# board.net
KiCad netlist of a schematic drawn in EAGLE
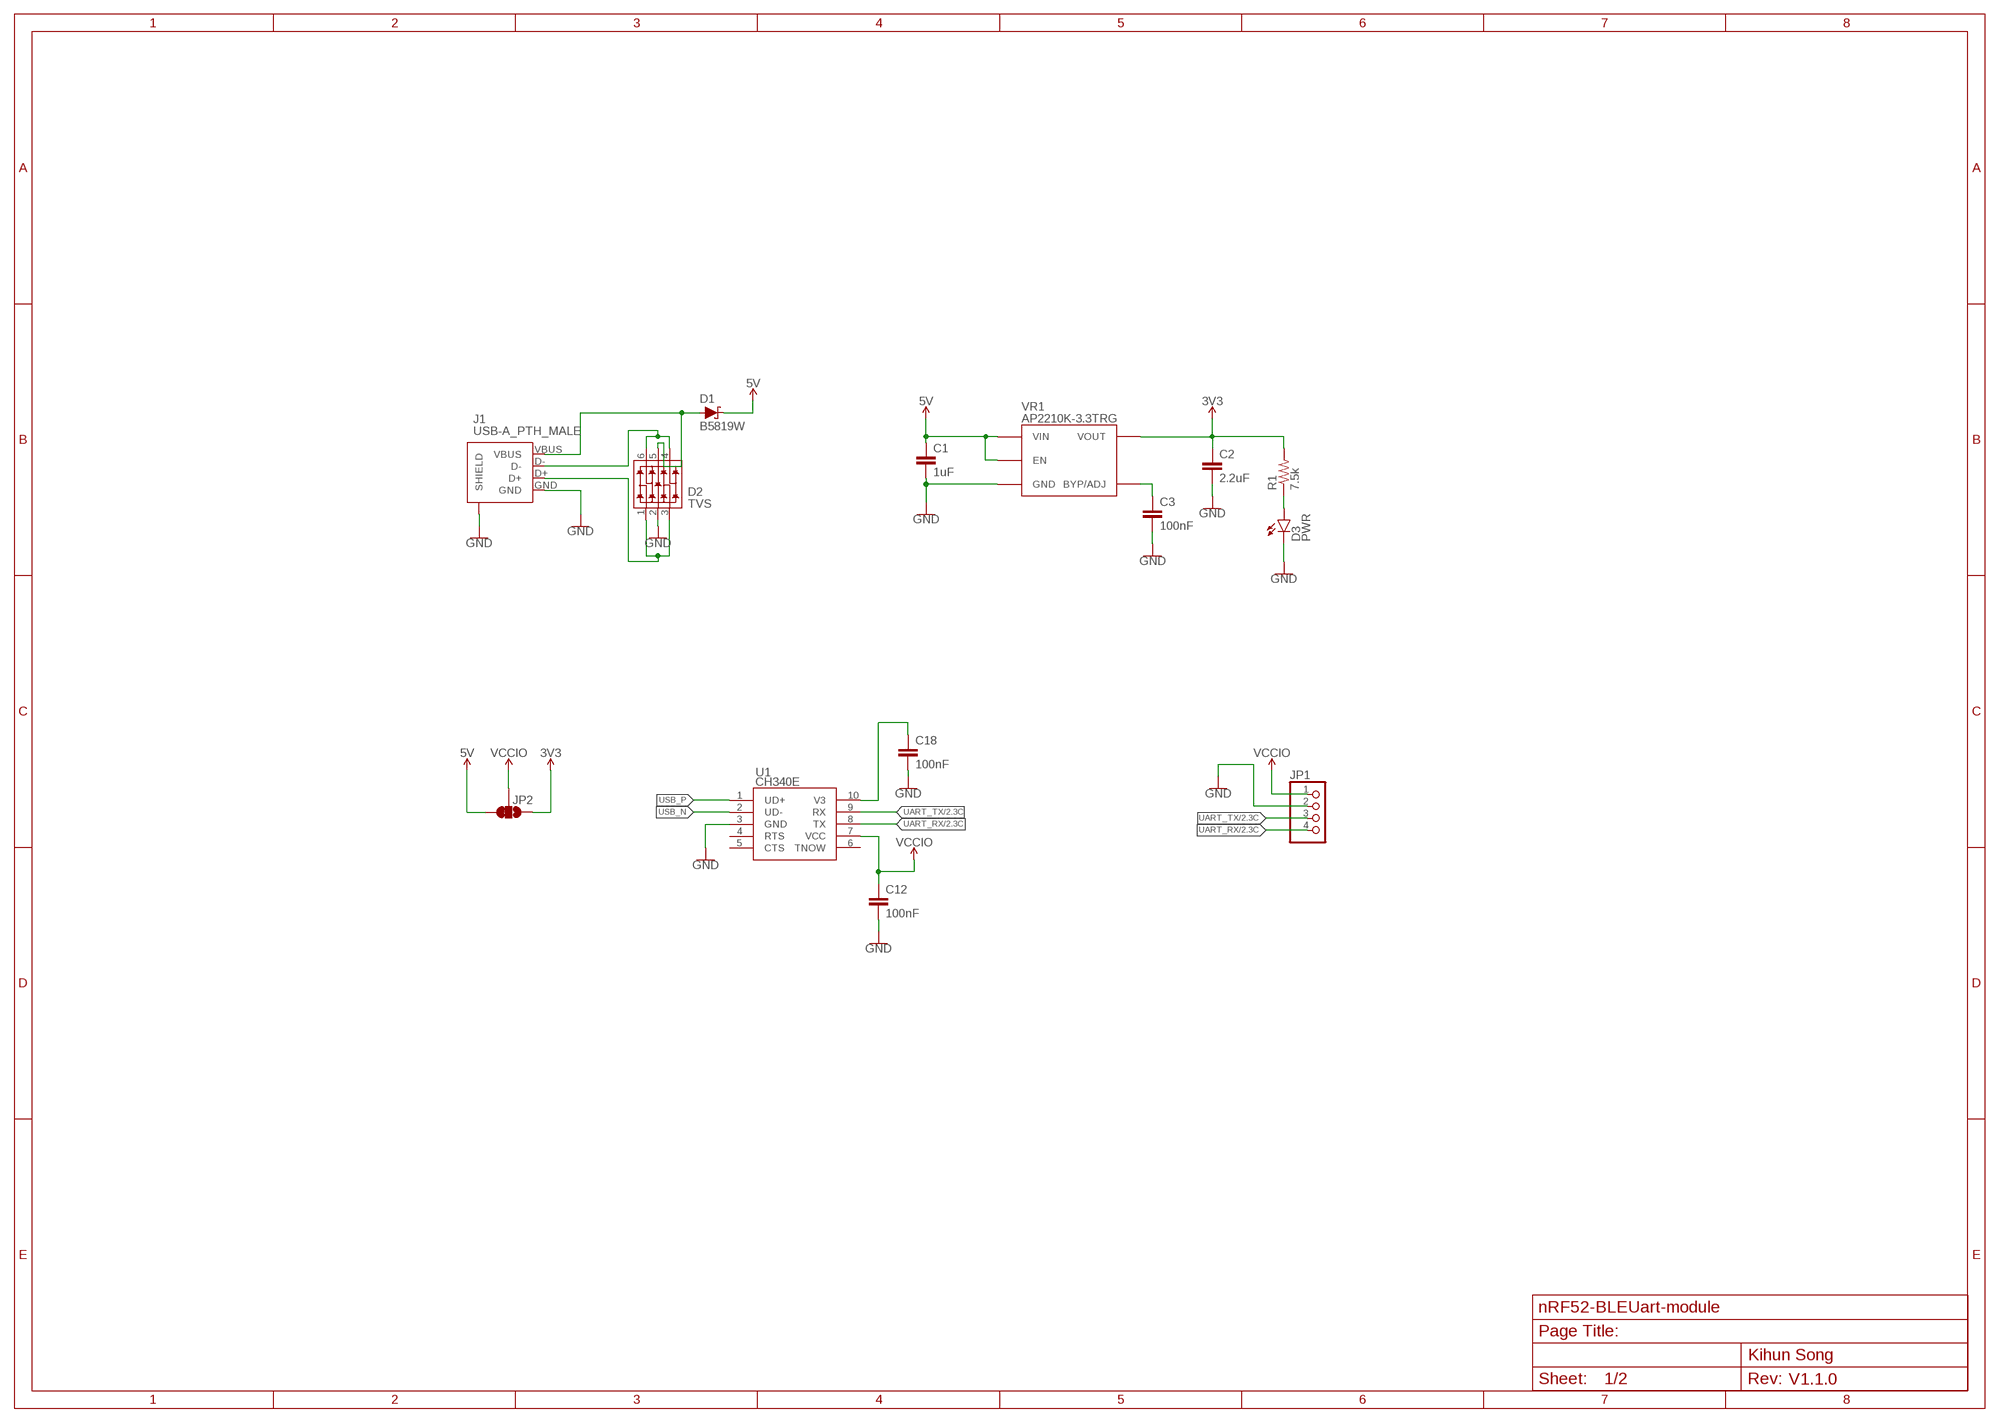
[diagram p0: schematic, sheet 1]
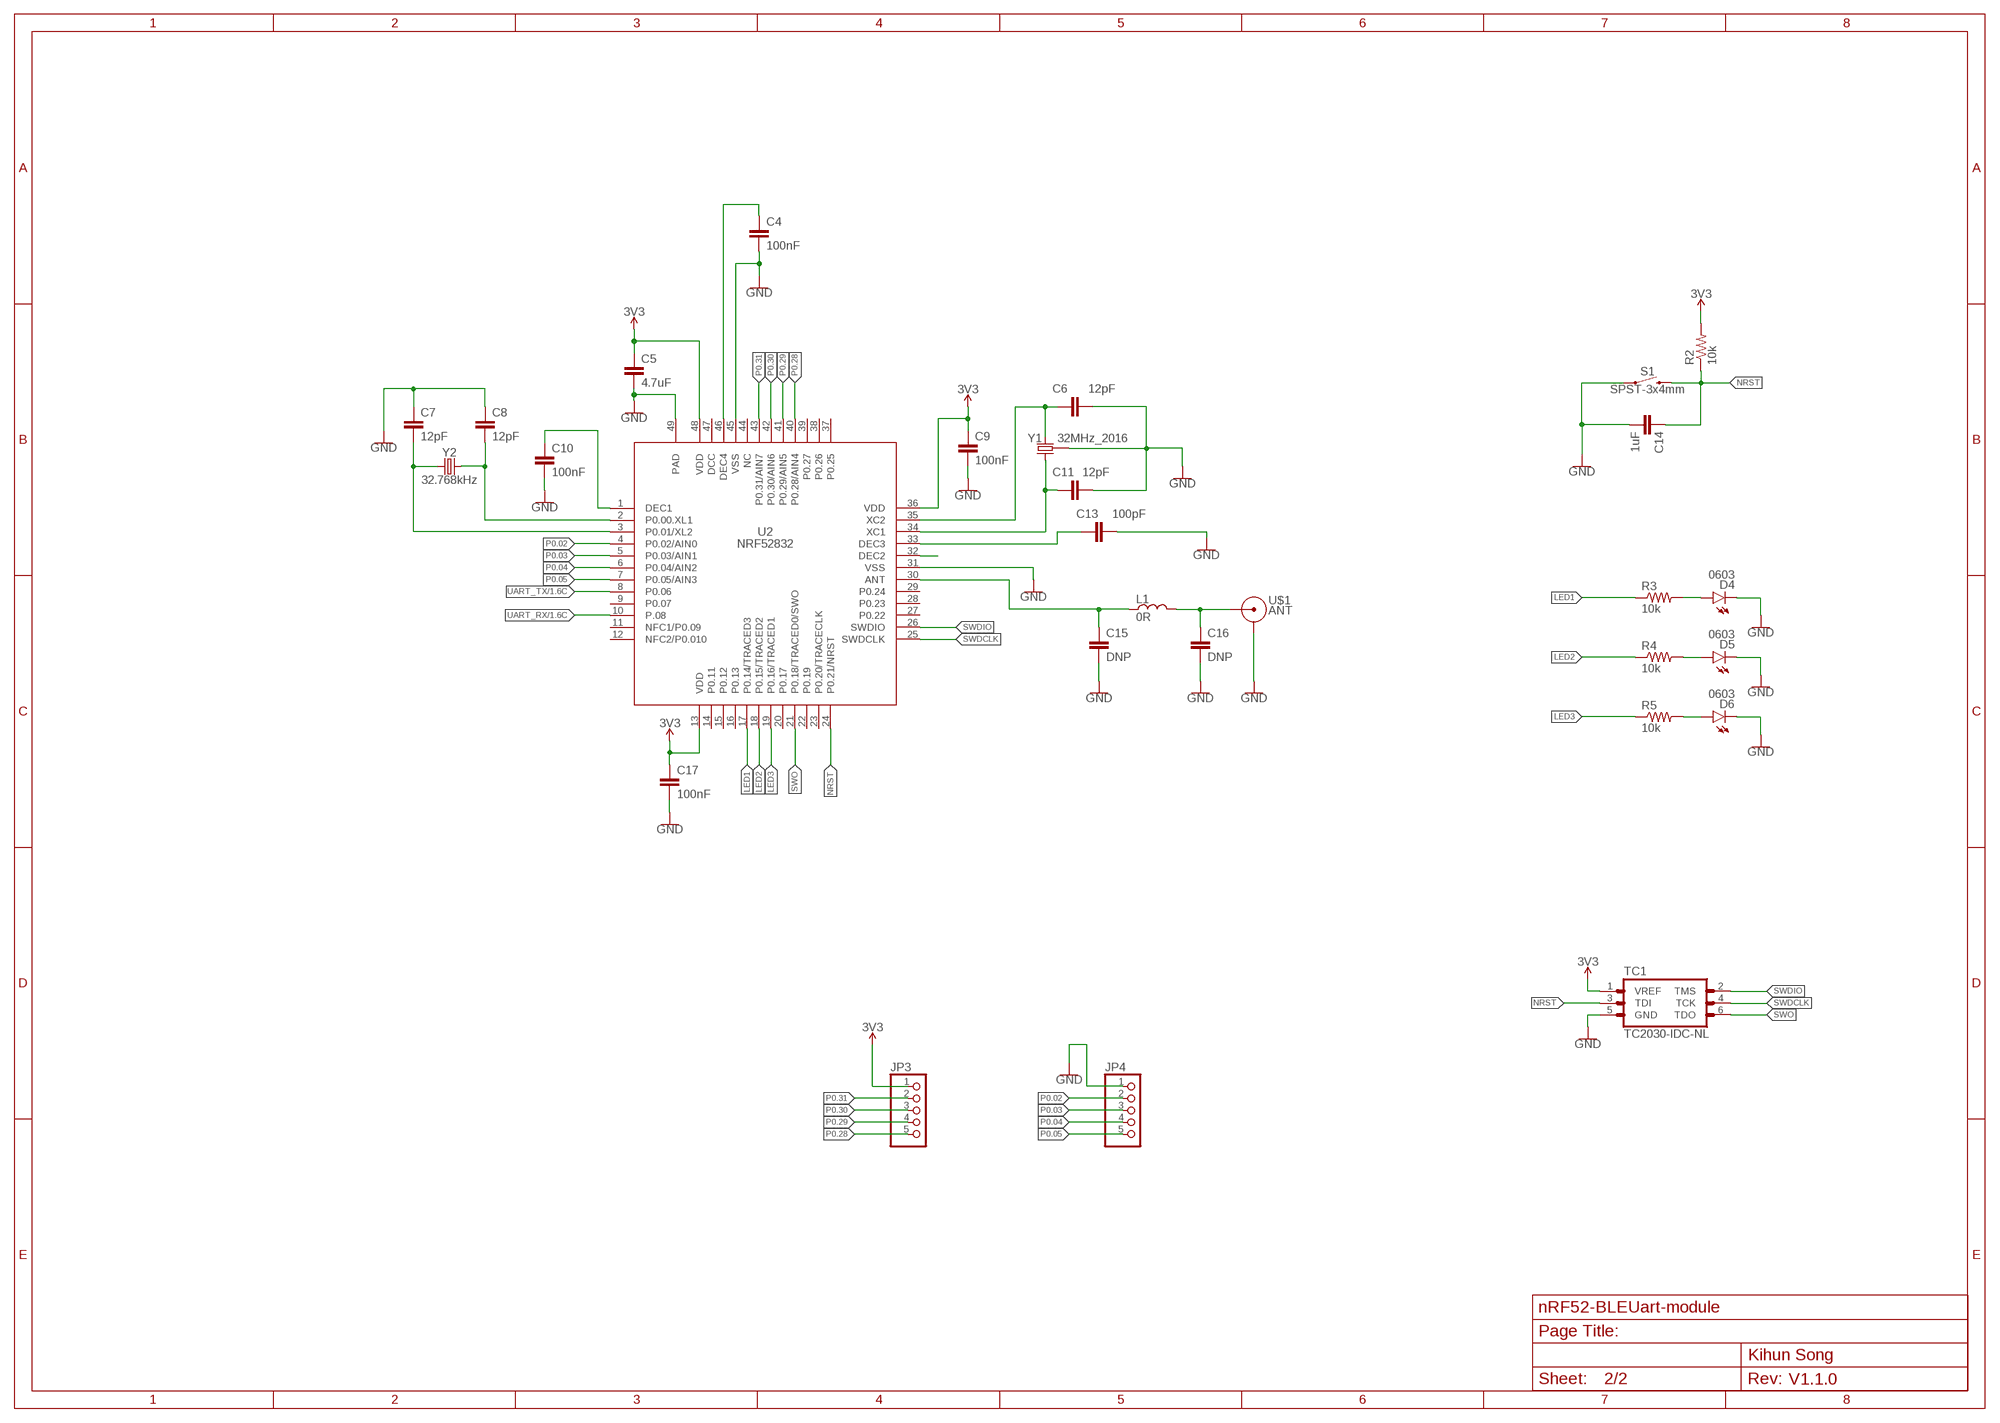
[diagram p1: schematic, sheet 2]

(export (version "E")
  (design (tool "Eeschema 10.0.6"))
  (components
    (comp (ref "C4")
      (value "100nF")
      (footprint "eagle-import:C0402")
      (libsource (lib "eagle-import") (part "C-NON-POLC0402"))
    )
    (comp (ref "C5")
      (value "4.7uF")
      (footprint "eagle-import:C0402")
      (libsource (lib "eagle-import") (part "C-NON-POLC0402"))
    )
    (comp (ref "C6")
      (value "12pF")
      (footprint "eagle-import:C0402")
      (libsource (lib "eagle-import") (part "C-NON-POLC0402"))
    )
    (comp (ref "C7")
      (value "12pF")
      (footprint "eagle-import:C0402")
      (libsource (lib "eagle-import") (part "C-NON-POLC0402"))
    )
    (comp (ref "C8")
      (value "12pF")
      (footprint "eagle-import:C0402")
      (libsource (lib "eagle-import") (part "C-NON-POLC0402"))
    )
    (comp (ref "C9")
      (value "100nF")
      (footprint "eagle-import:C0402")
      (libsource (lib "eagle-import") (part "C-NON-POLC0402"))
    )
    (comp (ref "C10")
      (value "100nF")
      (footprint "eagle-import:C0402")
      (libsource (lib "eagle-import") (part "C-NON-POLC0402"))
    )
    (comp (ref "C11")
      (value "12pF")
      (footprint "eagle-import:C0402")
      (libsource (lib "eagle-import") (part "C-NON-POLC0402"))
    )
    (comp (ref "C13")
      (value "100pF")
      (footprint "eagle-import:C0402")
      (libsource (lib "eagle-import") (part "C-NON-POLC0402"))
    )
    (comp (ref "C14")
      (value "1uF")
      (footprint "eagle-import:C0402")
      (libsource (lib "eagle-import") (part "C-NON-POLC0402"))
    )
    (comp (ref "C15")
      (value "DNP")
      (footprint "eagle-import:C0402")
      (libsource (lib "eagle-import") (part "C-NON-POLC0402"))
    )
    (comp (ref "C16")
      (value "DNP")
      (footprint "eagle-import:C0402")
      (libsource (lib "eagle-import") (part "C-NON-POLC0402"))
    )
    (comp (ref "C17")
      (value "100nF")
      (footprint "eagle-import:C0402")
      (libsource (lib "eagle-import") (part "C-NON-POLC0402"))
    )
    (comp (ref "D4")
      (value "0603")
      (footprint "eagle-import:LED_0603")
      (libsource (lib "eagle-import") (part "LED_0603"))
    )
    (comp (ref "D5")
      (value "0603")
      (footprint "eagle-import:LED_0603")
      (libsource (lib "eagle-import") (part "LED_0603"))
    )
    (comp (ref "D6")
      (value "0603")
      (footprint "eagle-import:LED_0603")
      (libsource (lib "eagle-import") (part "LED_0603"))
    )
    (comp (ref "JP3")
      (value "PINHD-1X5-NOSILK")
      (footprint "eagle-import:1X05-NOSILK")
      (libsource (lib "eagle-import") (part "PINHD-1X5-NOSILK"))
    )
    (comp (ref "JP4")
      (value "PINHD-1X5-NOSILK")
      (footprint "eagle-import:1X05-NOSILK")
      (libsource (lib "eagle-import") (part "PINHD-1X5-NOSILK"))
    )
    (comp (ref "L1")
      (value "0R")
      (footprint "eagle-import:R0402")
      (libsource (lib "eagle-import") (part "L0402"))
    )
    (comp (ref "R2")
      (value "10k")
      (footprint "eagle-import:R0402")
      (libsource (lib "eagle-import") (part "RR0402"))
    )
    (comp (ref "R3")
      (value "10k")
      (footprint "eagle-import:R0402")
      (libsource (lib "eagle-import") (part "RR0402"))
    )
    (comp (ref "R4")
      (value "10k")
      (footprint "eagle-import:R0402")
      (libsource (lib "eagle-import") (part "RR0402"))
    )
    (comp (ref "R5")
      (value "10k")
      (footprint "eagle-import:R0402")
      (libsource (lib "eagle-import") (part "RR0402"))
    )
    (comp (ref "S1")
      (value "SPST-3x4mm")
      (footprint "eagle-import:TACTILE_SWITCH_SMD_3.0X4.0MM")
      (libsource (lib "eagle-import") (part "SWITCH-SPST-SMD-3.0X4.0MM"))
    )
    (comp (ref "TC1")
      (value "TC2030-IDC-NL")
      (footprint "eagle-import:TC2030-IDC-NL")
      (libsource (lib "eagle-import") (part "TC2030-IDC-NL"))
    )
    (comp (ref "U$1")
      (value "ANT")
      (footprint "eagle-import:TI-AN043_LEFT_SHORTER")
      (libsource (lib "eagle-import") (part "INVERTED_F_2.4GHZ_TI-AN043_L_SHORT"))
    )
    (comp (ref "U2")
      (value "NRF52832")
      (footprint "eagle-import:QFN40P600X600X90-49T450N")
      (libsource (lib "eagle-import") (part "NRF52832"))
    )
    (comp (ref "Y1")
      (value "32MHz_2016")
      (footprint "eagle-import:CRYSTAL-SMD-2.0X1.6MM")
      (libsource (lib "eagle-import") (part "CRYSTAL-2.0X1.6MM"))
    )
    (comp (ref "Y2")
      (value "32.768kHz")
      (footprint "eagle-import:CRYSTAL-SMD-3.2X1.5MM")
      (libsource (lib "eagle-import") (part "CRYSTAL-32.768KHZ_3215"))
    )
    (comp (ref "C1")
      (value "1uF")
      (footprint "eagle-import:C0402")
      (libsource (lib "eagle-import") (part "C-NON-POLC0402"))
    )
    (comp (ref "C2")
      (value "2.2uF")
      (footprint "eagle-import:C0603")
      (libsource (lib "eagle-import") (part "C-NON-POLC0603"))
    )
    (comp (ref "C3")
      (value "100nF")
      (footprint "eagle-import:C0402")
      (libsource (lib "eagle-import") (part "C-NON-POLC0402"))
    )
    (comp (ref "C12")
      (value "100nF")
      (footprint "eagle-import:C0402")
      (libsource (lib "eagle-import") (part "C-NON-POLC0402"))
    )
    (comp (ref "C18")
      (value "100nF")
      (footprint "eagle-import:C0402")
      (libsource (lib "eagle-import") (part "C-NON-POLC0402"))
    )
    (comp (ref "D1")
      (value "B5819W")
      (footprint "eagle-import:SOD-123")
      (libsource (lib "eagle-import") (part "DIODE-SCHOTTKY_SOD-123"))
    )
    (comp (ref "D2")
      (value "TVS")
      (footprint "eagle-import:SPT-23-6")
      (libsource (lib "eagle-import") (part "TVS-ARRAY_SOT-23-6"))
    )
    (comp (ref "D3")
      (value "PWR")
      (footprint "eagle-import:LED_0603")
      (libsource (lib "eagle-import") (part "LED_0603"))
    )
    (comp (ref "J1")
      (value "USB-A_PTH_MALE")
      (footprint "eagle-import:USB-A-MALE-H-PTH-1")
      (libsource (lib "eagle-import") (part "USB-A_PTH_MALE-U-G-O4DD-W-1"))
    )
    (comp (ref "JP1")
      (value "Rx Tx G V")
      (footprint "eagle-import:1X04-NOSILK")
      (libsource (lib "eagle-import") (part "PINHD-1X4NOSILK"))
    )
    (comp (ref "JP2")
      (value "5V 3V3")
      (footprint "eagle-import:SMT-JUMPER_3_1-NC_TRACE_NO-SILK")
      (libsource (lib "eagle-import") (part "JUMPER-SMT_3_1-NC_TRACE_NO-SILK"))
    )
    (comp (ref "R1")
      (value "7.5k")
      (footprint "eagle-import:R0402")
      (libsource (lib "eagle-import") (part "RR0402"))
    )
    (comp (ref "U1")
      (value "CH340E")
      (footprint "eagle-import:MSOP-10")
      (libsource (lib "eagle-import") (part "CH340E"))
    )
    (comp (ref "VR1")
      (value "AP2210K-3.3TRG")
      (footprint "eagle-import:SOT-23-5")
      (libsource (lib "eagle-import") (part "AP2210K"))
    )
  )
  (nets
    (net (code "1") (name "3V3") (class "Default")
      (node (ref "C17") (pin "1") (pinfunction "1_1") (pintype "passive"))
      (node (ref "C2") (pin "1") (pinfunction "1_1") (pintype "passive"))
      (node (ref "C5") (pin "1") (pinfunction "1_1") (pintype "passive"))
      (node (ref "C9") (pin "1") (pinfunction "1_1") (pintype "passive"))
      (node (ref "JP2") (pin "1") (pinfunction "1_1") (pintype "passive"))
      (node (ref "JP3") (pin "1") (pinfunction "1_1") (pintype "passive"))
      (node (ref "R1") (pin "2") (pinfunction "2_2") (pintype "passive"))
      (node (ref "R2") (pin "2") (pinfunction "2_2") (pintype "passive"))
      (node (ref "TC1") (pin "1") (pinfunction "VREF_1") (pintype "passive"))
      (node (ref "U2") (pin "13") (pinfunction "VDD_13") (pintype "bidirectional"))
      (node (ref "U2") (pin "36") (pinfunction "VDD_36") (pintype "bidirectional"))
      (node (ref "U2") (pin "48") (pinfunction "VDD_48") (pintype "bidirectional"))
      (node (ref "VR1") (pin "5") (pinfunction "VOUT_5") (pintype "output"))
    )
    (net (code "2") (name "5V") (class "Default")
      (node (ref "C1") (pin "1") (pinfunction "1_1") (pintype "passive"))
      (node (ref "D1") (pin "C") (pinfunction "C_C") (pintype "passive"))
      (node (ref "JP2") (pin "3") (pinfunction "3_3") (pintype "passive"))
      (node (ref "VR1") (pin "1") (pinfunction "VIN_1") (pintype "input"))
      (node (ref "VR1") (pin "3") (pinfunction "EN_3") (pintype "bidirectional"))
    )
    (net (code "3") (name "GND") (class "Default")
      (node (ref "C1") (pin "2") (pinfunction "2_2") (pintype "passive"))
      (node (ref "C10") (pin "2") (pinfunction "2_2") (pintype "passive"))
      (node (ref "C11") (pin "2") (pinfunction "2_2") (pintype "passive"))
      (node (ref "C12") (pin "2") (pinfunction "2_2") (pintype "passive"))
      (node (ref "C13") (pin "2") (pinfunction "2_2") (pintype "passive"))
      (node (ref "C14") (pin "2") (pinfunction "2_2") (pintype "passive"))
      (node (ref "C15") (pin "2") (pinfunction "2_2") (pintype "passive"))
      (node (ref "C16") (pin "2") (pinfunction "2_2") (pintype "passive"))
      (node (ref "C17") (pin "2") (pinfunction "2_2") (pintype "passive"))
      (node (ref "C18") (pin "2") (pinfunction "2_2") (pintype "passive"))
      (node (ref "C2") (pin "2") (pinfunction "2_2") (pintype "passive"))
      (node (ref "C3") (pin "2") (pinfunction "2_2") (pintype "passive"))
      (node (ref "C4") (pin "2") (pinfunction "2_2") (pintype "passive"))
      (node (ref "C5") (pin "2") (pinfunction "2_2") (pintype "passive"))
      (node (ref "C6") (pin "2") (pinfunction "2_2") (pintype "passive"))
      (node (ref "C7") (pin "1") (pinfunction "1_1") (pintype "passive"))
      (node (ref "C8") (pin "1") (pinfunction "1_1") (pintype "passive"))
      (node (ref "C9") (pin "2") (pinfunction "2_2") (pintype "passive"))
      (node (ref "D2") (pin "2") (pinfunction "VSS_2") (pintype "bidirectional"))
      (node (ref "D3") (pin "C") (pinfunction "C_C") (pintype "passive"))
      (node (ref "D4") (pin "C") (pinfunction "C_C") (pintype "passive"))
      (node (ref "D5") (pin "C") (pinfunction "C_C") (pintype "passive"))
      (node (ref "D6") (pin "C") (pinfunction "C_C") (pintype "passive"))
      (node (ref "J1") (pin "GND") (pinfunction "GND_GND") (pintype "power_in"))
      (node (ref "J1") (pin "SHIELD@0") (pinfunction "SHIELD_SHIELD@0") (pintype "bidirectional"))
      (node (ref "J1") (pin "SHIELD@1") (pinfunction "SHIELD_SHIELD@1") (pintype "bidirectional"))
      (node (ref "J1") (pin "SHIELD@2") (pinfunction "SHIELD_SHIELD@2") (pintype "bidirectional"))
      (node (ref "J1") (pin "SHIELD@3") (pinfunction "SHIELD_SHIELD@3") (pintype "bidirectional"))
      (node (ref "JP1") (pin "2") (pinfunction "2_2") (pintype "passive"))
      (node (ref "JP4") (pin "1") (pinfunction "1_1") (pintype "passive"))
      (node (ref "S1") (pin "1") (pinfunction "1_1") (pintype "passive"))
      (node (ref "TC1") (pin "5") (pinfunction "GND_5") (pintype "passive"))
      (node (ref "U$1") (pin "GND") (pinfunction "GND_GND") (pintype "bidirectional"))
      (node (ref "U1") (pin "3") (pinfunction "GND_3") (pintype "power_in"))
      (node (ref "U2") (pin "31") (pinfunction "VSS_31") (pintype "bidirectional"))
      (node (ref "U2") (pin "45") (pinfunction "VSS_45") (pintype "bidirectional"))
      (node (ref "U2") (pin "49") (pinfunction "PAD_49") (pintype "bidirectional"))
      (node (ref "VR1") (pin "2") (pinfunction "GND_2") (pintype "power_in"))
      (node (ref "Y1") (pin "2") (pinfunction "GND_2") (pintype "power_in"))
      (node (ref "Y1") (pin "4") (pinfunction "GND_4") (pintype "power_in"))
    )
    (net (code "4") (name "LED1") (class "Default")
      (node (ref "R3") (pin "1") (pinfunction "1_1") (pintype "passive"))
      (node (ref "U2") (pin "17") (pinfunction "P0.14/TRACED3_17") (pintype "bidirectional"))
    )
    (net (code "5") (name "LED2") (class "Default")
      (node (ref "R4") (pin "1") (pinfunction "1_1") (pintype "passive"))
      (node (ref "U2") (pin "18") (pinfunction "P0.15/TRACED2_18") (pintype "bidirectional"))
    )
    (net (code "6") (name "LED3") (class "Default")
      (node (ref "R5") (pin "1") (pinfunction "1_1") (pintype "passive"))
      (node (ref "U2") (pin "19") (pinfunction "P0.16/TRACED1_19") (pintype "bidirectional"))
    )
    (net (code "7") (name "NRST") (class "Default")
      (node (ref "C14") (pin "1") (pinfunction "1_1") (pintype "passive"))
      (node (ref "R2") (pin "1") (pinfunction "1_1") (pintype "passive"))
      (node (ref "S1") (pin "2") (pinfunction "2_2") (pintype "passive"))
      (node (ref "TC1") (pin "3") (pinfunction "TDI_3") (pintype "passive"))
      (node (ref "U2") (pin "24") (pinfunction "P0.21/NRST_24") (pintype "bidirectional"))
    )
    (net (code "8") (name "Net-(D2-VCC)") (class "Default")
      (node (ref "D1") (pin "A") (pinfunction "A_A") (pintype "passive"))
      (node (ref "D2") (pin "5") (pinfunction "VCC_5") (pintype "bidirectional"))
      (node (ref "J1") (pin "VBUS") (pinfunction "VBUS_VBUS") (pintype "power_in"))
    )
    (net (code "9") (name "Net-(D3-PadA)") (class "Default")
      (node (ref "D3") (pin "A") (pinfunction "A_A") (pintype "passive"))
      (node (ref "R1") (pin "1") (pinfunction "1_1") (pintype "passive"))
    )
    (net (code "10") (name "Net-(D4-PadA)") (class "Default")
      (node (ref "D4") (pin "A") (pinfunction "A_A") (pintype "passive"))
      (node (ref "R3") (pin "2") (pinfunction "2_2") (pintype "passive"))
    )
    (net (code "11") (name "Net-(D5-PadA)") (class "Default")
      (node (ref "D5") (pin "A") (pinfunction "A_A") (pintype "passive"))
      (node (ref "R4") (pin "2") (pinfunction "2_2") (pintype "passive"))
    )
    (net (code "12") (name "Net-(D6-PadA)") (class "Default")
      (node (ref "D6") (pin "A") (pinfunction "A_A") (pintype "passive"))
      (node (ref "R5") (pin "2") (pinfunction "2_2") (pintype "passive"))
    )
    (net (code "13") (name "Net-(U$1-FEED)") (class "Default")
      (node (ref "C16") (pin "1") (pinfunction "1_1") (pintype "passive"))
      (node (ref "L1") (pin "2") (pinfunction "2_2") (pintype "passive"))
      (node (ref "U$1") (pin "RF") (pinfunction "FEED_RF") (pintype "bidirectional"))
    )
    (net (code "14") (name "Net-(U1-V3)") (class "Default")
      (node (ref "C18") (pin "1") (pinfunction "1_1") (pintype "passive"))
      (node (ref "U1") (pin "10") (pinfunction "V3_10") (pintype "power_in"))
    )
    (net (code "15") (name "Net-(U2-ANT)") (class "Default")
      (node (ref "C15") (pin "1") (pinfunction "1_1") (pintype "passive"))
      (node (ref "L1") (pin "1") (pinfunction "1_1") (pintype "passive"))
      (node (ref "U2") (pin "30") (pinfunction "ANT_30") (pintype "bidirectional"))
    )
    (net (code "16") (name "Net-(U2-DEC1)") (class "Default")
      (node (ref "C10") (pin "1") (pinfunction "1_1") (pintype "passive"))
      (node (ref "U2") (pin "1") (pinfunction "DEC1_1") (pintype "bidirectional"))
    )
    (net (code "17") (name "Net-(U2-DEC3)") (class "Default")
      (node (ref "C13") (pin "1") (pinfunction "1_1") (pintype "passive"))
      (node (ref "U2") (pin "33") (pinfunction "DEC3_33") (pintype "bidirectional"))
    )
    (net (code "18") (name "Net-(U2-DEC4)") (class "Default")
      (node (ref "C4") (pin "1") (pinfunction "1_1") (pintype "passive"))
      (node (ref "U2") (pin "46") (pinfunction "DEC4_46") (pintype "bidirectional"))
    )
    (net (code "19") (name "Net-(U2-P0.00.XL1)") (class "Default")
      (node (ref "C8") (pin "2") (pinfunction "2_2") (pintype "passive"))
      (node (ref "U2") (pin "2") (pinfunction "P0.00.XL1_2") (pintype "bidirectional"))
      (node (ref "Y2") (pin "P$2") (pinfunction "2_P$2") (pintype "passive"))
    )
    (net (code "20") (name "Net-(U2-P0.01{slash}XL2)") (class "Default")
      (node (ref "C7") (pin "2") (pinfunction "2_2") (pintype "passive"))
      (node (ref "U2") (pin "3") (pinfunction "P0.01/XL2_3") (pintype "bidirectional"))
      (node (ref "Y2") (pin "P$1") (pinfunction "1_P$1") (pintype "passive"))
    )
    (net (code "21") (name "Net-(U2-XC1)") (class "Default")
      (node (ref "C11") (pin "1") (pinfunction "1_1") (pintype "passive"))
      (node (ref "U2") (pin "34") (pinfunction "XC1_34") (pintype "bidirectional"))
      (node (ref "Y1") (pin "1") (pinfunction "1_1") (pintype "passive"))
    )
    (net (code "22") (name "Net-(U2-XC2)") (class "Default")
      (node (ref "C6") (pin "1") (pinfunction "1_1") (pintype "passive"))
      (node (ref "U2") (pin "35") (pinfunction "XC2_35") (pintype "bidirectional"))
      (node (ref "Y1") (pin "3") (pinfunction "2_3") (pintype "passive"))
    )
    (net (code "23") (name "Net-(VR1-BYP{slash}ADJ)") (class "Default")
      (node (ref "C3") (pin "1") (pinfunction "1_1") (pintype "passive"))
      (node (ref "VR1") (pin "4") (pinfunction "BYP/ADJ_4") (pintype "bidirectional"))
    )
    (net (code "24") (name "P0.02") (class "Default")
      (node (ref "JP4") (pin "2") (pinfunction "2_2") (pintype "passive"))
      (node (ref "U2") (pin "4") (pinfunction "P0.02/AIN0_4") (pintype "bidirectional"))
    )
    (net (code "25") (name "P0.03") (class "Default")
      (node (ref "JP4") (pin "3") (pinfunction "3_3") (pintype "passive"))
      (node (ref "U2") (pin "5") (pinfunction "P0.03/AIN1_5") (pintype "bidirectional"))
    )
    (net (code "26") (name "P0.04") (class "Default")
      (node (ref "JP4") (pin "4") (pinfunction "4_4") (pintype "passive"))
      (node (ref "U2") (pin "6") (pinfunction "P0.04/AIN2_6") (pintype "bidirectional"))
    )
    (net (code "27") (name "P0.05") (class "Default")
      (node (ref "JP4") (pin "5") (pinfunction "5_5") (pintype "passive"))
      (node (ref "U2") (pin "7") (pinfunction "P0.05/AIN3_7") (pintype "bidirectional"))
    )
    (net (code "28") (name "P0.28") (class "Default")
      (node (ref "JP3") (pin "5") (pinfunction "5_5") (pintype "passive"))
      (node (ref "U2") (pin "40") (pinfunction "P0.28/AIN4_40") (pintype "bidirectional"))
    )
    (net (code "29") (name "P0.29") (class "Default")
      (node (ref "JP3") (pin "4") (pinfunction "4_4") (pintype "passive"))
      (node (ref "U2") (pin "41") (pinfunction "P0.29/AIN5_41") (pintype "bidirectional"))
    )
    (net (code "30") (name "P0.30") (class "Default")
      (node (ref "JP3") (pin "3") (pinfunction "3_3") (pintype "passive"))
      (node (ref "U2") (pin "42") (pinfunction "P0.30/AIN6_42") (pintype "bidirectional"))
    )
    (net (code "31") (name "P0.31") (class "Default")
      (node (ref "JP3") (pin "2") (pinfunction "2_2") (pintype "passive"))
      (node (ref "U2") (pin "43") (pinfunction "P0.31/AIN7_43") (pintype "bidirectional"))
    )
    (net (code "32") (name "SWDCLK") (class "Default")
      (node (ref "TC1") (pin "4") (pinfunction "TCK_4") (pintype "passive"))
      (node (ref "U2") (pin "25") (pinfunction "SWDCLK_25") (pintype "bidirectional"))
    )
    (net (code "33") (name "SWDIO") (class "Default")
      (node (ref "TC1") (pin "2") (pinfunction "TMS_2") (pintype "passive"))
      (node (ref "U2") (pin "26") (pinfunction "SWDIO_26") (pintype "bidirectional"))
    )
    (net (code "34") (name "SWO") (class "Default")
      (node (ref "TC1") (pin "6") (pinfunction "TDO_6") (pintype "passive"))
      (node (ref "U2") (pin "21") (pinfunction "P0.18/TRACED0/SWO_21") (pintype "bidirectional"))
    )
    (net (code "35") (name "UART_RX") (class "Default")
      (node (ref "JP1") (pin "4") (pinfunction "4_4") (pintype "passive"))
      (node (ref "U1") (pin "8") (pinfunction "TX_8") (pintype "output"))
      (node (ref "U2") (pin "10") (pinfunction "P.08_10") (pintype "bidirectional"))
    )
    (net (code "36") (name "UART_TX") (class "Default")
      (node (ref "JP1") (pin "3") (pinfunction "3_3") (pintype "passive"))
      (node (ref "U1") (pin "9") (pinfunction "RX_9") (pintype "input"))
      (node (ref "U2") (pin "8") (pinfunction "P0.06_8") (pintype "bidirectional"))
    )
    (net (code "37") (name "USB_N") (class "Default")
      (node (ref "D2") (pin "4") (pinfunction "IO3_4") (pintype "bidirectional"))
      (node (ref "D2") (pin "6") (pinfunction "IO4_6") (pintype "bidirectional"))
      (node (ref "J1") (pin "D-") (pinfunction "D-_D-") (pintype "bidirectional"))
      (node (ref "U1") (pin "2") (pinfunction "UD-_2") (pintype "bidirectional"))
    )
    (net (code "38") (name "USB_P") (class "Default")
      (node (ref "D2") (pin "1") (pinfunction "IO1_1") (pintype "bidirectional"))
      (node (ref "D2") (pin "3") (pinfunction "IO2_3") (pintype "bidirectional"))
      (node (ref "J1") (pin "D+") (pinfunction "D+_D+") (pintype "bidirectional"))
      (node (ref "U1") (pin "1") (pinfunction "UD+_1") (pintype "bidirectional"))
    )
    (net (code "39") (name "VCCIO") (class "Default")
      (node (ref "C12") (pin "1") (pinfunction "1_1") (pintype "passive"))
      (node (ref "JP1") (pin "1") (pinfunction "1_1") (pintype "passive"))
      (node (ref "JP2") (pin "2") (pinfunction "2_2") (pintype "passive"))
      (node (ref "U1") (pin "7") (pinfunction "VCC_7") (pintype "power_in"))
    )
    (net (code "40") (name "unconnected-(U1-CTS-Pad5)") (class "Default")
      (node (ref "U1") (pin "5") (pinfunction "CTS_5") (pintype "input"))
    )
    (net (code "41") (name "unconnected-(U1-RTS-Pad4)") (class "Default")
      (node (ref "U1") (pin "4") (pinfunction "RTS_4") (pintype "output"))
    )
    (net (code "42") (name "unconnected-(U1-TNOW-Pad6)") (class "Default")
      (node (ref "U1") (pin "6") (pinfunction "TNOW_6") (pintype "output"))
    )
    (net (code "43") (name "unconnected-(U2-DCC-Pad47)") (class "Default")
      (node (ref "U2") (pin "47") (pinfunction "DCC_47") (pintype "bidirectional"))
    )
    (net (code "44") (name "unconnected-(U2-DEC2-Pad32)") (class "Default")
      (node (ref "U2") (pin "32") (pinfunction "DEC2_32") (pintype "bidirectional"))
    )
    (net (code "45") (name "unconnected-(U2-NC-Pad44)") (class "Default")
      (node (ref "U2") (pin "44") (pinfunction "NC_44") (pintype "no_connect"))
    )
    (net (code "46") (name "unconnected-(U2-NFC1{slash}P0.09-Pad11)") (class "Default")
      (node (ref "U2") (pin "11") (pinfunction "NFC1/P0.09_11") (pintype "bidirectional"))
    )
    (net (code "47") (name "unconnected-(U2-NFC2{slash}P0.010-Pad12)") (class "Default")
      (node (ref "U2") (pin "12") (pinfunction "NFC2/P0.010_12") (pintype "bidirectional"))
    )
    (net (code "48") (name "unconnected-(U2-P0.07-Pad9)") (class "Default")
      (node (ref "U2") (pin "9") (pinfunction "P0.07_9") (pintype "bidirectional"))
    )
    (net (code "49") (name "unconnected-(U2-P0.11-Pad14)") (class "Default")
      (node (ref "U2") (pin "14") (pinfunction "P0.11_14") (pintype "bidirectional"))
    )
    (net (code "50") (name "unconnected-(U2-P0.12-Pad15)") (class "Default")
      (node (ref "U2") (pin "15") (pinfunction "P0.12_15") (pintype "bidirectional"))
    )
    (net (code "51") (name "unconnected-(U2-P0.13-Pad16)") (class "Default")
      (node (ref "U2") (pin "16") (pinfunction "P0.13_16") (pintype "bidirectional"))
    )
    (net (code "52") (name "unconnected-(U2-P0.17-Pad20)") (class "Default")
      (node (ref "U2") (pin "20") (pinfunction "P0.17_20") (pintype "bidirectional"))
    )
    (net (code "53") (name "unconnected-(U2-P0.19-Pad22)") (class "Default")
      (node (ref "U2") (pin "22") (pinfunction "P0.19_22") (pintype "bidirectional"))
    )
    (net (code "54") (name "unconnected-(U2-P0.20{slash}TRACECLK-Pad23)") (class "Default")
      (node (ref "U2") (pin "23") (pinfunction "P0.20/TRACECLK_23") (pintype "bidirectional"))
    )
    (net (code "55") (name "unconnected-(U2-P0.22-Pad27)") (class "Default")
      (node (ref "U2") (pin "27") (pinfunction "P0.22_27") (pintype "bidirectional"))
    )
    (net (code "56") (name "unconnected-(U2-P0.23-Pad28)") (class "Default")
      (node (ref "U2") (pin "28") (pinfunction "P0.23_28") (pintype "bidirectional"))
    )
    (net (code "57") (name "unconnected-(U2-P0.24-Pad29)") (class "Default")
      (node (ref "U2") (pin "29") (pinfunction "P0.24_29") (pintype "bidirectional"))
    )
    (net (code "58") (name "unconnected-(U2-P0.25-Pad37)") (class "Default")
      (node (ref "U2") (pin "37") (pinfunction "P0.25_37") (pintype "bidirectional"))
    )
    (net (code "59") (name "unconnected-(U2-P0.26-Pad38)") (class "Default")
      (node (ref "U2") (pin "38") (pinfunction "P0.26_38") (pintype "bidirectional"))
    )
    (net (code "60") (name "unconnected-(U2-P0.27-Pad39)") (class "Default")
      (node (ref "U2") (pin "39") (pinfunction "P0.27_39") (pintype "bidirectional"))
    )
  )
)
